# DualPowerSupply.net
KiCad netlist of a schematic drawn in EAGLE
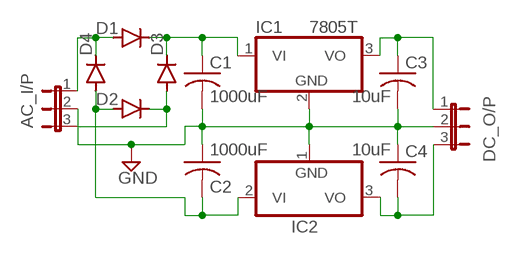
[diagram p0: schematic, sheet 1]

(export (version "E")
  (design (tool "Eeschema 10.0.6"))
  (components
    (comp (ref "AC_I/P")
      (value "JP2E")
      (footprint "eagle-import:JP2")
      (libsource (lib "eagle-import") (part "JP2E"))
    )
    (comp (ref "C1")
      (value "1000uF")
      (footprint "eagle-import:C025_050-025X075")
      (libsource (lib "eagle-import") (part "C-US025_050-025X075"))
    )
    (comp (ref "C2")
      (value "1000uF")
      (footprint "eagle-import:C025_050-025X075")
      (libsource (lib "eagle-import") (part "C-US025_050-025X075"))
    )
    (comp (ref "C3")
      (value "10uF")
      (footprint "eagle-import:C025_050-025X075")
      (libsource (lib "eagle-import") (part "C-US025_050-025X075"))
    )
    (comp (ref "C4")
      (value "10uF")
      (footprint "eagle-import:C025_050-025X075")
      (libsource (lib "eagle-import") (part "C-US025_050-025X075"))
    )
    (comp (ref "D1")
      (value "1N4004")
      (footprint "eagle-import:DO41-10")
      (libsource (lib "eagle-import") (part "1N4004"))
    )
    (comp (ref "D2")
      (value "1N4004")
      (footprint "eagle-import:DO41-10")
      (libsource (lib "eagle-import") (part "1N4004"))
    )
    (comp (ref "D3")
      (value "1N4004")
      (footprint "eagle-import:DO41-10")
      (libsource (lib "eagle-import") (part "1N4004"))
    )
    (comp (ref "D4")
      (value "1N4004")
      (footprint "eagle-import:DO41-10")
      (libsource (lib "eagle-import") (part "1N4004"))
    )
    (comp (ref "DC_O/P")
      (value "JP2E")
      (footprint "eagle-import:JP2")
      (libsource (lib "eagle-import") (part "JP2E"))
    )
    (comp (ref "IC1")
      (value "7805T")
      (footprint "eagle-import:TO220H")
      (libsource (lib "eagle-import") (part "78T05"))
    )
    (comp (ref "IC2")
      (value "7905T")
      (footprint "eagle-import:TO220H")
      (libsource (lib "eagle-import") (part "79T05"))
    )
  )
  (nets
    (net (code "1") (name "GND") (class "Default")
      (node (ref "AC_I/P") (pin "2") (pinfunction "2_2") (pintype "passive"))
      (node (ref "C1") (pin "2") (pinfunction "2_2") (pintype "passive"))
      (node (ref "C2") (pin "1") (pinfunction "1_1") (pintype "passive"))
      (node (ref "C3") (pin "2") (pinfunction "2_2") (pintype "passive"))
      (node (ref "C4") (pin "1") (pinfunction "1_1") (pintype "passive"))
      (node (ref "DC_O/P") (pin "2") (pinfunction "2_2") (pintype "passive"))
      (node (ref "IC1") (pin "2") (pinfunction "GND_2") (pintype "passive"))
      (node (ref "IC2") (pin "1") (pinfunction "GND_1") (pintype "passive"))
    )
    (net (code "2") (name "Net-(AC_I/P-Pad1)") (class "Default")
      (node (ref "AC_I/P") (pin "1") (pinfunction "1_1") (pintype "passive"))
      (node (ref "D1") (pin "A") (pinfunction "A_A") (pintype "passive"))
      (node (ref "D4") (pin "C") (pinfunction "C_C") (pintype "passive"))
    )
    (net (code "3") (name "Net-(AC_I/P-Pad3)") (class "Default")
      (node (ref "AC_I/P") (pin "3") (pinfunction "3_3") (pintype "passive"))
      (node (ref "D2") (pin "C") (pinfunction "C_C") (pintype "passive"))
      (node (ref "D3") (pin "A") (pinfunction "A_A") (pintype "passive"))
    )
    (net (code "4") (name "Net-(IC1-VI)") (class "Default")
      (node (ref "C1") (pin "1") (pinfunction "1_1") (pintype "passive"))
      (node (ref "D1") (pin "C") (pinfunction "C_C") (pintype "passive"))
      (node (ref "D3") (pin "C") (pinfunction "C_C") (pintype "passive"))
      (node (ref "IC1") (pin "1") (pinfunction "VI_1") (pintype "input"))
    )
    (net (code "5") (name "Net-(IC1-VO)") (class "Default")
      (node (ref "C3") (pin "1") (pinfunction "1_1") (pintype "passive"))
      (node (ref "DC_O/P") (pin "1") (pinfunction "1_1") (pintype "passive"))
      (node (ref "IC1") (pin "3") (pinfunction "VO_3") (pintype "passive"))
    )
    (net (code "6") (name "Net-(IC2-VI)") (class "Default")
      (node (ref "C2") (pin "2") (pinfunction "2_2") (pintype "passive"))
      (node (ref "D2") (pin "A") (pinfunction "A_A") (pintype "passive"))
      (node (ref "D4") (pin "A") (pinfunction "A_A") (pintype "passive"))
      (node (ref "IC2") (pin "2") (pinfunction "VI_2") (pintype "input"))
    )
    (net (code "7") (name "Net-(IC2-VO)") (class "Default")
      (node (ref "C4") (pin "2") (pinfunction "2_2") (pintype "passive"))
      (node (ref "DC_O/P") (pin "3") (pinfunction "3_3") (pintype "passive"))
      (node (ref "IC2") (pin "3") (pinfunction "VO_3") (pintype "passive"))
    )
  )
)
